# Main.net
KiCad netlist of a schematic drawn in Altium Designer
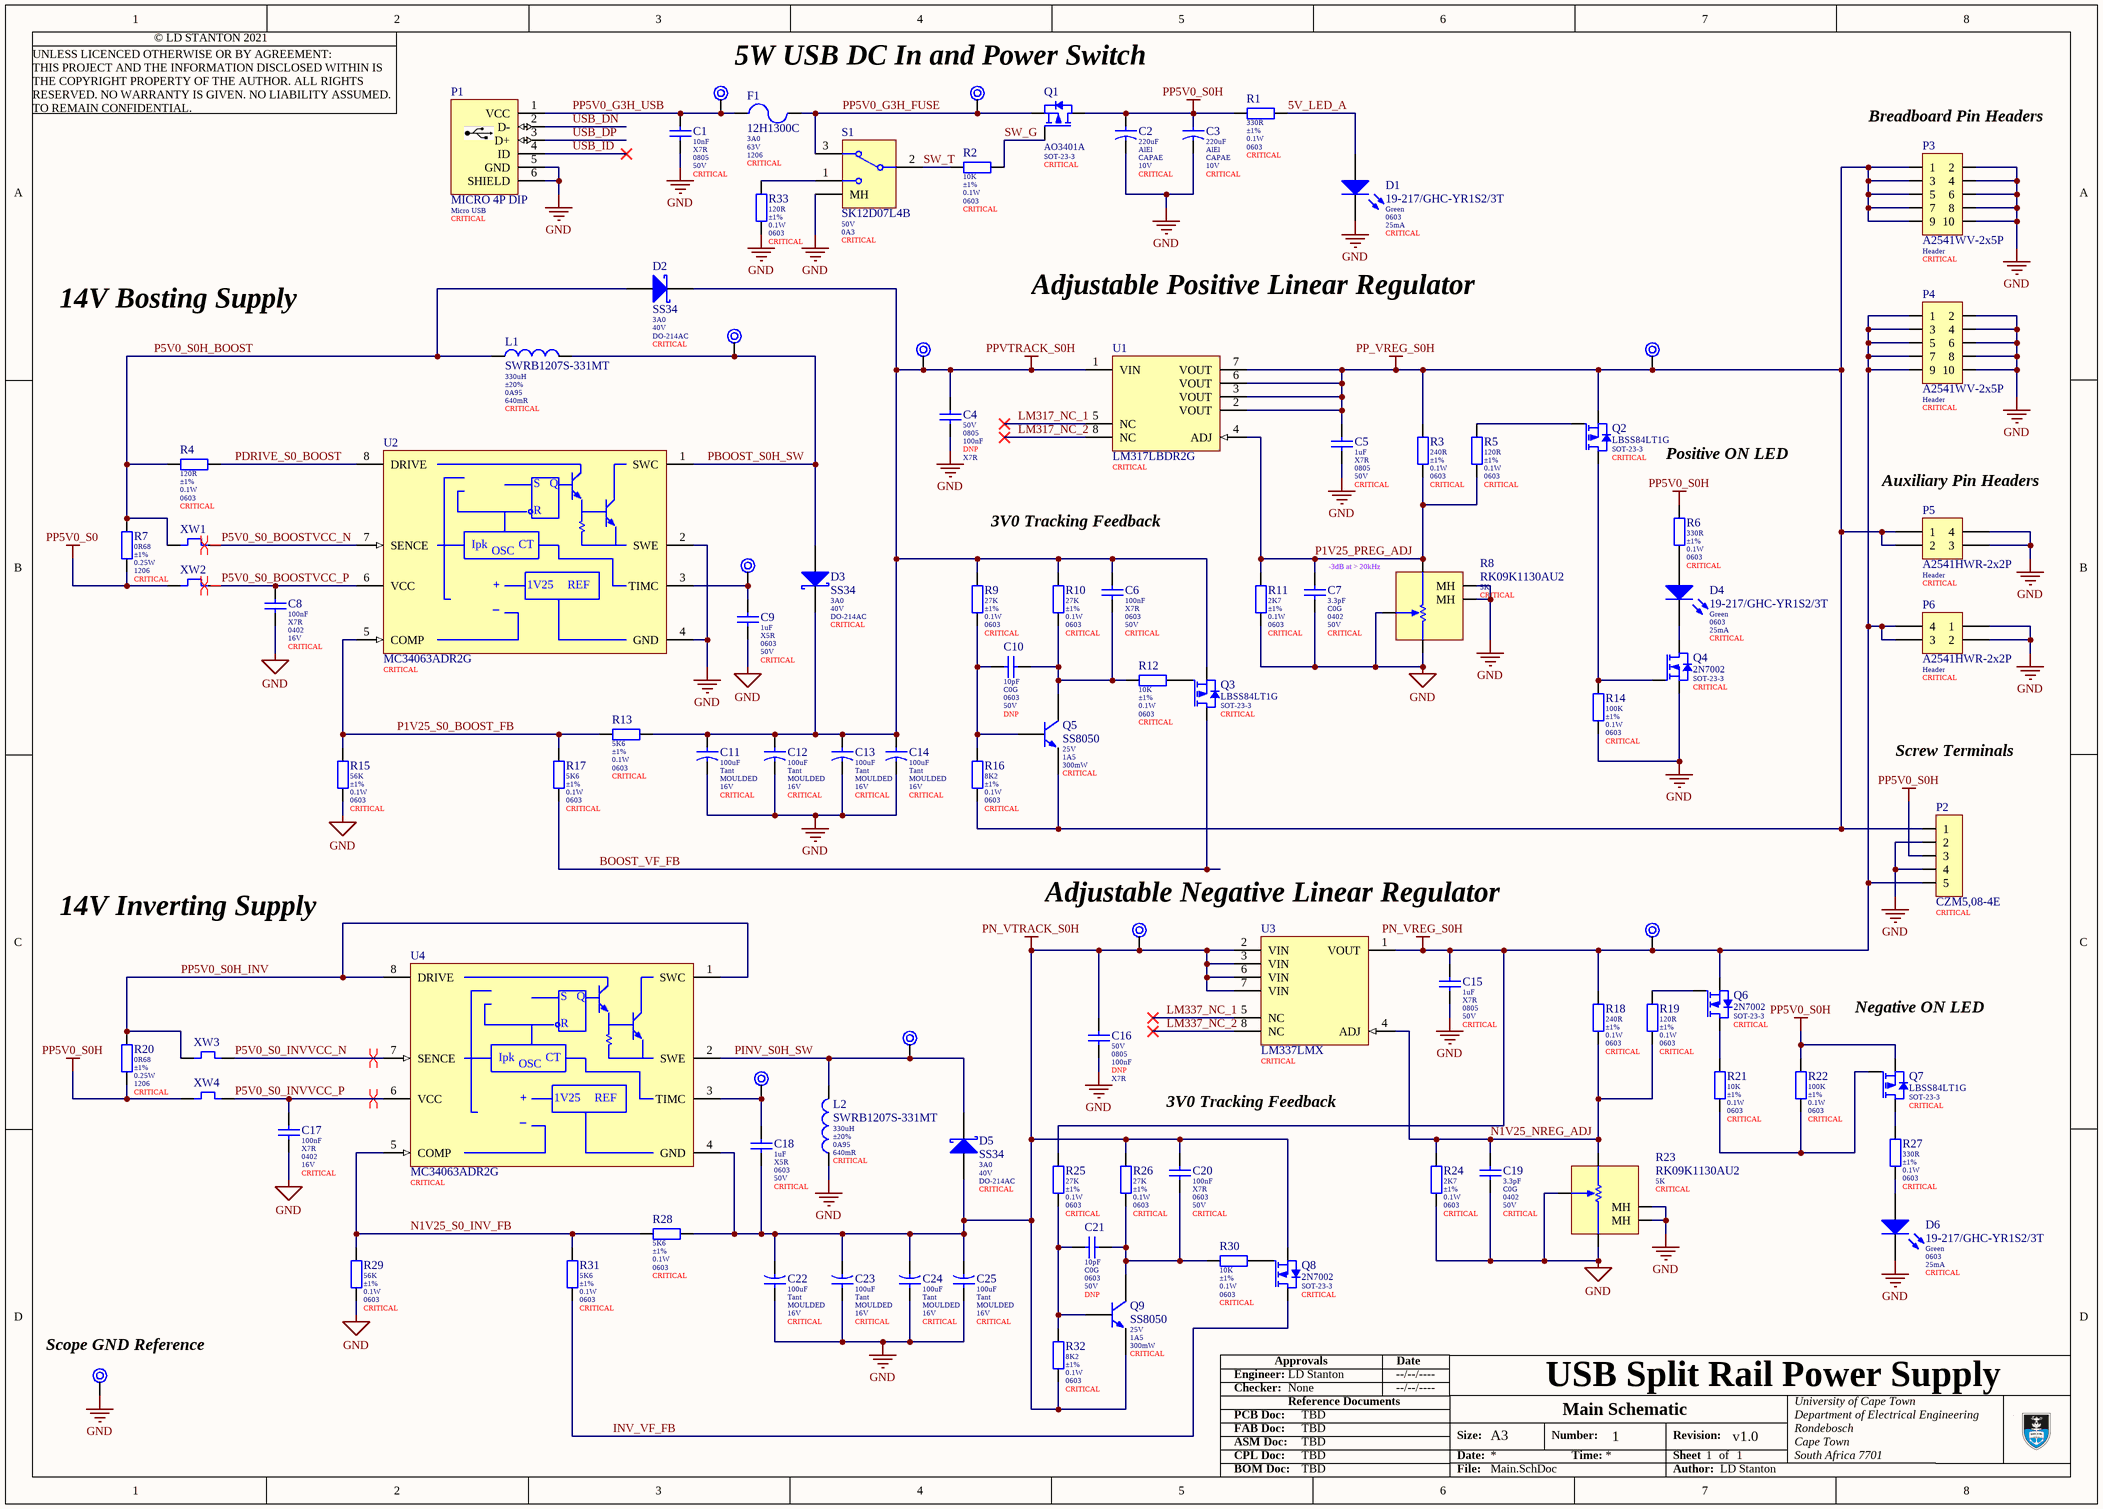
[diagram p0: Main.SchDoc]

(export (version "E")
  (design (tool "Eeschema 10.0.6"))
  (components
    (comp (ref "C1")
      (value "10nF")
      (footprint "0605_065_A_N")
      (description "MLCC 10nF 0805 50V X7R ±10%")
      (fields
        (field (name "TOLERANCE") "±10%")
        (field (name "LCSC PART NUMBER") "C1710")
        (field (name "DIELECTRIC") "X7R")
        (field (name "PACKAGE") "0805")
        (field (name "VOLTAGE") "50V")
        (field (name "POPULATE") "CRITICAL")
      )
      (libsource (lib "Samsung Capacitors") (part "MLCC 10nF 0805 50V X7R"))
    )
    (comp (ref "C2")
      (value "220uF")
      (footprint "CAPAE 6354")
      (description "Aluminium Electrolytic Capacitor 220uF CAPAE 10V ±20%")
      (fields
        (field (name "TOLERANCE") "±20%")
        (field (name "LCSC PART NUMBER") "C3345")
        (field (name "DIELECTRIC") "AlEl")
        (field (name "PACKAGE") "CAPAE")
        (field (name "VOLTAGE") "10V")
        (field (name "POPULATE") "CRITICAL")
      )
      (libsource (lib "JLCPCB Electrolytic Capacitors") (part "Cap AlEl 220uF 10V"))
    )
    (comp (ref "C3")
      (value "220uF")
      (footprint "CAPAE 6354")
      (description "Aluminium Electrolytic Capacitor 220uF CAPAE 10V ±20%")
      (fields
        (field (name "TOLERANCE") "±20%")
        (field (name "LCSC PART NUMBER") "C3345")
        (field (name "DIELECTRIC") "AlEl")
        (field (name "PACKAGE") "CAPAE")
        (field (name "VOLTAGE") "10V")
        (field (name "POPULATE") "CRITICAL")
      )
      (libsource (lib "JLCPCB Electrolytic Capacitors") (part "Cap AlEl 220uF 10V"))
    )
    (comp (ref "C4")
      (value "100nF")
      (footprint "0805")
      (description "MLCC 100nF 50V 0805 X7R ±10%")
      (fields
        (field (name "TOLERANCE") "±10%")
        (field (name "LCSC PART NUMBER") "C49678")
        (field (name "VOLTAGE") "50V")
        (field (name "PACKAGE") "0805")
        (field (name "POPULATE") "DNP")
        (field (name "DIELECTRIC") "X7R")
      )
      (libsource (lib "Yageo Capacitors") (part "MLCC 100nF 50V 0805 X7R"))
    )
    (comp (ref "C5")
      (value "1uF")
      (footprint "0805_125_F_N")
      (description "MLCC 1uF 0805 50V X7R ±10%")
      (fields
        (field (name "TOLERANCE") "±10%")
        (field (name "LCSC PART NUMBER") "C15849")
        (field (name "DIELECTRIC") "X7R")
        (field (name "PACKAGE") "0805")
        (field (name "VOLTAGE") "50V")
        (field (name "POPULATE") "CRITICAL")
      )
      (libsource (lib "Samsung Capacitors") (part "MLCC 1uF 0805 50V X7R"))
    )
    (comp (ref "C6")
      (value "100nF")
      (footprint "0603")
      (description "MLCC 100nF 50V 0603 X7R ±10%")
      (fields
        (field (name "TOLERANCE") "±10%")
        (field (name "LCSC PART NUMBER") "C14663")
        (field (name "DIELECTRIC") "X7R")
        (field (name "PACKAGE") "0603")
        (field (name "VOLTAGE") "50V")
        (field (name "POPULATE") "CRITICAL")
      )
      (libsource (lib "Yageo Capacitors") (part "MLCC 100nF 50V 0603 X7R"))
    )
    (comp (ref "C7")
      (value "3.3pF")
      (footprint "0402_050")
      (description "MLCC 3.3pF 0402 50V C0G ±0.25pF")
      (fields
        (field (name "TOLERANCE") "±0.25pF")
        (field (name "LCSC PART NUMBER") "C1565")
        (field (name "DIELECTRIC") "C0G")
        (field (name "PACKAGE") "0402")
        (field (name "VOLTAGE") "50V")
        (field (name "POPULATE") "CRITICAL")
      )
      (libsource (lib "Guangdong Capacitors") (part "MLCC 3.3pF 0402 50V C0G"))
    )
    (comp (ref "C8")
      (value "100nF")
      (footprint "0402_050_5_N")
      (description "MLCC 100nF 0402 16V X7R ±10%")
      (fields
        (field (name "TOLERANCE") "±10%")
        (field (name "LCSC PART NUMBER") "C1525")
        (field (name "DIELECTRIC") "X7R")
        (field (name "PACKAGE") "0402")
        (field (name "VOLTAGE") "16V")
        (field (name "POPULATE") "CRITICAL")
      )
      (libsource (lib "Samsung Capacitors") (part "MLCC 100nF 0402 16V X7R"))
    )
    (comp (ref "C9")
      (value "1uF")
      (footprint "0603_080_8_N")
      (description "MLCC 1uF 0603 50V X5R ±10%")
      (fields
        (field (name "TOLERANCE") "±10%")
        (field (name "LCSC PART NUMBER") "C15849")
        (field (name "DIELECTRIC") "X5R")
        (field (name "PACKAGE") "0603")
        (field (name "VOLTAGE") "50V")
        (field (name "POPULATE") "CRITICAL")
      )
      (libsource (lib "Samsung Capacitors") (part "MLCC 1uF 0603 50V X5R"))
    )
    (comp (ref "C10")
      (value "10pF")
      (footprint "0603_080_8_N")
      (description "MLCC 10pF 0603 C0G ±0.1pF")
      (fields
        (field (name "TOLERANCE") "±0.1pF")
        (field (name "LCSC PART NUMBER") "C1634")
        (field (name "DIELECTRIC") "C0G")
        (field (name "PACKAGE") "0603")
        (field (name "VOLTAGE") "50V")
        (field (name "POPULATE") "DNP")
      )
      (libsource (lib "Samsung Capacitors") (part "MLCC 10pF 0603 50V C0G"))
    )
    (comp (ref "C11")
      (value "100uF")
      (footprint "Case D")
      (description "Tantalum Capacitor 100uF 16V ±20%")
      (fields
        (field (name "TOLERANCE") "±20%")
        (field (name "LCSC PART NUMBER") "C129696")
        (field (name "DIELECTRIC") "Tant")
        (field (name "PACKAGE") "MOULDED")
        (field (name "VOLTAGE") "16V")
        (field (name "POPULATE") "CRITICAL")
      )
      (libsource (lib "Tantalums Vishay") (part "Cap Tant 100uF 16V"))
    )
    (comp (ref "C12")
      (value "100uF")
      (footprint "Case D")
      (description "Tantalum Capacitor 100uF 16V ±20%")
      (fields
        (field (name "TOLERANCE") "±20%")
        (field (name "LCSC PART NUMBER") "C129696")
        (field (name "DIELECTRIC") "Tant")
        (field (name "PACKAGE") "MOULDED")
        (field (name "VOLTAGE") "16V")
        (field (name "POPULATE") "CRITICAL")
      )
      (libsource (lib "Tantalums Vishay") (part "Cap Tant 100uF 16V"))
    )
    (comp (ref "C13")
      (value "100uF")
      (footprint "Case D")
      (description "Tantalum Capacitor 100uF 16V ±20%")
      (fields
        (field (name "TOLERANCE") "±20%")
        (field (name "LCSC PART NUMBER") "C129696")
        (field (name "DIELECTRIC") "Tant")
        (field (name "PACKAGE") "MOULDED")
        (field (name "VOLTAGE") "16V")
        (field (name "POPULATE") "CRITICAL")
      )
      (libsource (lib "Tantalums Vishay") (part "Cap Tant 100uF 16V"))
    )
    (comp (ref "C14")
      (value "100uF")
      (footprint "Case D")
      (description "Tantalum Capacitor 100uF 16V ±20%")
      (fields
        (field (name "TOLERANCE") "±20%")
        (field (name "LCSC PART NUMBER") "C129696")
        (field (name "DIELECTRIC") "Tant")
        (field (name "PACKAGE") "MOULDED")
        (field (name "VOLTAGE") "16V")
        (field (name "POPULATE") "CRITICAL")
      )
      (libsource (lib "Tantalums Vishay") (part "Cap Tant 100uF 16V"))
    )
    (comp (ref "C15")
      (value "1uF")
      (footprint "0805_125_F_N")
      (description "MLCC 1uF 0805 50V X7R ±10%")
      (fields
        (field (name "TOLERANCE") "±10%")
        (field (name "LCSC PART NUMBER") "C15849")
        (field (name "DIELECTRIC") "X7R")
        (field (name "PACKAGE") "0805")
        (field (name "VOLTAGE") "50V")
        (field (name "POPULATE") "CRITICAL")
      )
      (libsource (lib "Samsung Capacitors") (part "MLCC 1uF 0805 50V X7R"))
    )
    (comp (ref "C16")
      (value "100nF")
      (footprint "0805")
      (description "MLCC 100nF 50V 0805 X7R ±10%")
      (fields
        (field (name "TOLERANCE") "±10%")
        (field (name "LCSC PART NUMBER") "C49678")
        (field (name "VOLTAGE") "50V")
        (field (name "PACKAGE") "0805")
        (field (name "POPULATE") "DNP")
        (field (name "DIELECTRIC") "X7R")
      )
      (libsource (lib "Yageo Capacitors") (part "MLCC 100nF 50V 0805 X7R"))
    )
    (comp (ref "C17")
      (value "100nF")
      (footprint "0402_050_5_N")
      (description "MLCC 100nF 0402 16V X7R ±10%")
      (fields
        (field (name "TOLERANCE") "±10%")
        (field (name "LCSC PART NUMBER") "C1525")
        (field (name "DIELECTRIC") "X7R")
        (field (name "PACKAGE") "0402")
        (field (name "VOLTAGE") "16V")
        (field (name "POPULATE") "CRITICAL")
      )
      (libsource (lib "Samsung Capacitors") (part "MLCC 100nF 0402 16V X7R"))
    )
    (comp (ref "C18")
      (value "1uF")
      (footprint "0603_080_8_N")
      (description "MLCC 1uF 0603 50V X5R ±10%")
      (fields
        (field (name "TOLERANCE") "±10%")
        (field (name "LCSC PART NUMBER") "C15849")
        (field (name "DIELECTRIC") "X5R")
        (field (name "PACKAGE") "0603")
        (field (name "VOLTAGE") "50V")
        (field (name "POPULATE") "CRITICAL")
      )
      (libsource (lib "Samsung Capacitors") (part "MLCC 1uF 0603 50V X5R"))
    )
    (comp (ref "C19")
      (value "3.3pF")
      (footprint "0402_050")
      (description "MLCC 3.3pF 0402 50V C0G ±0.25pF")
      (fields
        (field (name "TOLERANCE") "±0.25pF")
        (field (name "LCSC PART NUMBER") "C1565")
        (field (name "DIELECTRIC") "C0G")
        (field (name "PACKAGE") "0402")
        (field (name "VOLTAGE") "50V")
        (field (name "POPULATE") "CRITICAL")
      )
      (libsource (lib "Guangdong Capacitors") (part "MLCC 3.3pF 0402 50V C0G"))
    )
    (comp (ref "C20")
      (value "100nF")
      (footprint "0603")
      (description "MLCC 100nF 50V 0603 X7R ±10%")
      (fields
        (field (name "TOLERANCE") "±10%")
        (field (name "LCSC PART NUMBER") "C14663")
        (field (name "DIELECTRIC") "X7R")
        (field (name "PACKAGE") "0603")
        (field (name "VOLTAGE") "50V")
        (field (name "POPULATE") "CRITICAL")
      )
      (libsource (lib "Yageo Capacitors") (part "MLCC 100nF 50V 0603 X7R"))
    )
    (comp (ref "C21")
      (value "10pF")
      (footprint "0603_080_8_N")
      (description "MLCC 10pF 0603 C0G ±0.1pF")
      (fields
        (field (name "TOLERANCE") "±0.1pF")
        (field (name "LCSC PART NUMBER") "C1634")
        (field (name "DIELECTRIC") "C0G")
        (field (name "PACKAGE") "0603")
        (field (name "VOLTAGE") "50V")
        (field (name "POPULATE") "DNP")
      )
      (libsource (lib "Samsung Capacitors") (part "MLCC 10pF 0603 50V C0G"))
    )
    (comp (ref "C22")
      (value "100uF")
      (footprint "Case D")
      (description "Tantalum Capacitor 100uF 16V ±20%")
      (fields
        (field (name "TOLERANCE") "±20%")
        (field (name "LCSC PART NUMBER") "C129696")
        (field (name "DIELECTRIC") "Tant")
        (field (name "PACKAGE") "MOULDED")
        (field (name "VOLTAGE") "16V")
        (field (name "POPULATE") "CRITICAL")
      )
      (libsource (lib "Tantalums Vishay") (part "Cap Tant 100uF 16V"))
    )
    (comp (ref "C23")
      (value "100uF")
      (footprint "Case D")
      (description "Tantalum Capacitor 100uF 16V ±20%")
      (fields
        (field (name "TOLERANCE") "±20%")
        (field (name "LCSC PART NUMBER") "C129696")
        (field (name "DIELECTRIC") "Tant")
        (field (name "PACKAGE") "MOULDED")
        (field (name "VOLTAGE") "16V")
        (field (name "POPULATE") "CRITICAL")
      )
      (libsource (lib "Tantalums Vishay") (part "Cap Tant 100uF 16V"))
    )
    (comp (ref "C24")
      (value "100uF")
      (footprint "Case D")
      (description "Tantalum Capacitor 100uF 16V ±20%")
      (fields
        (field (name "TOLERANCE") "±20%")
        (field (name "LCSC PART NUMBER") "C129696")
        (field (name "DIELECTRIC") "Tant")
        (field (name "PACKAGE") "MOULDED")
        (field (name "VOLTAGE") "16V")
        (field (name "POPULATE") "CRITICAL")
      )
      (libsource (lib "Tantalums Vishay") (part "Cap Tant 100uF 16V"))
    )
    (comp (ref "C25")
      (value "100uF")
      (footprint "Case D")
      (description "Tantalum Capacitor 100uF 16V ±20%")
      (fields
        (field (name "TOLERANCE") "±20%")
        (field (name "LCSC PART NUMBER") "C129696")
        (field (name "DIELECTRIC") "Tant")
        (field (name "PACKAGE") "MOULDED")
        (field (name "VOLTAGE") "16V")
        (field (name "POPULATE") "CRITICAL")
      )
      (libsource (lib "Tantalums Vishay") (part "Cap Tant 100uF 16V"))
    )
    (comp (ref "D1")
      (value "19-217/GHC-YR1S2/3T")
      (footprint "LED 0603")
      (description "LED 0603 SMT Green")
      (fields
        (field (name "LCSC PART NUMBER") "C72043")
        (field (name "COLOUR") "Green")
        (field (name "PACKAGE") "0603")
        (field (name "CURRENT") "25mA")
        (field (name "PLACEMENT") "CRITICAL")
      )
      (libsource (lib "JLCPCB LEDs") (part "LED 0603 Green"))
    )
    (comp (ref "D2")
      (value "SS34")
      (footprint "DO-214AC")
      (description "Schottky Barrier Diode 40V 3A0 550mV")
      (fields
        (field (name "LCSC PART NUMBER") "C8678")
        (field (name "MANUFACTURER") "MDD")
        (field (name "DC FORWARD CURENT") "3A0")
        (field (name "DC REVERSE BLOCKING") "40V")
        (field (name "PACKAGE") "DO-214AC")
        (field (name "PLACEMENT") "CRITICAL")
      )
      (libsource (lib "Schottky Barrier Diodes") (part "SS34"))
    )
    (comp (ref "D3")
      (value "SS34")
      (footprint "DO-214AC")
      (description "Schottky Barrier Diode 40V 3A0 550mV")
      (fields
        (field (name "LCSC PART NUMBER") "C8678")
        (field (name "MANUFACTURER") "MDD")
        (field (name "DC FORWARD CURENT") "3A0")
        (field (name "DC REVERSE BLOCKING") "40V")
        (field (name "PACKAGE") "DO-214AC")
        (field (name "PLACEMENT") "CRITICAL")
      )
      (libsource (lib "Schottky Barrier Diodes") (part "SS34"))
    )
    (comp (ref "D4")
      (value "19-217/GHC-YR1S2/3T")
      (footprint "LED 0603")
      (description "LED 0603 SMT Green")
      (fields
        (field (name "LCSC PART NUMBER") "C72043")
        (field (name "COLOUR") "Green")
        (field (name "PACKAGE") "0603")
        (field (name "CURRENT") "25mA")
        (field (name "PLACEMENT") "CRITICAL")
      )
      (libsource (lib "JLCPCB LEDs") (part "LED 0603 Green"))
    )
    (comp (ref "D5")
      (value "SS34")
      (footprint "DO-214AC")
      (description "Schottky Barrier Diode 40V 3A0 550mV")
      (fields
        (field (name "LCSC PART NUMBER") "C8678")
        (field (name "MANUFACTURER") "MDD")
        (field (name "DC FORWARD CURENT") "3A0")
        (field (name "DC REVERSE BLOCKING") "40V")
        (field (name "PACKAGE") "DO-214AC")
        (field (name "PLACEMENT") "CRITICAL")
      )
      (libsource (lib "Schottky Barrier Diodes") (part "SS34"))
    )
    (comp (ref "D6")
      (value "19-217/GHC-YR1S2/3T")
      (footprint "LED 0603")
      (description "LED 0603 SMT Green")
      (fields
        (field (name "LCSC PART NUMBER") "C72043")
        (field (name "COLOUR") "Green")
        (field (name "PACKAGE") "0603")
        (field (name "CURRENT") "25mA")
        (field (name "PLACEMENT") "CRITICAL")
      )
      (libsource (lib "JLCPCB LEDs") (part "LED 0603 Green"))
    )
    (comp (ref "F1")
      (value "12H1300C")
      (footprint "1206_060")
      (description "Fuse SMD Slow Blow 3A 63VAC 1206")
      (fields
        (field (name "LCSC PART NUMBER") "C182445")
        (field (name "CURRENT") "3A0")
        (field (name "VOLTAGE") "63V")
        (field (name "PACKAGE") "1206")
        (field (name "PLACEMENT") "CRITICAL")
      )
      (libsource (lib "Fuses") (part "Fuse 3A Slow 1206"))
    )
    (comp (ref "L1")
      (value "SWRB1207S-331MT")
      (footprint "SWRB1207S")
      (description "Inductor 330uH ±20% 0A95 640mR Moulded SMD 12.5x12.5x8.0mm")
      (fields
        (field (name "LCSC PART NUMBER") "C169381")
        (field (name "MANUFACTURER") "Sunlord")
        (field (name "ALTIUM_VALUE") "330uH")
        (field (name "TOLERANCE") "±20%")
        (field (name "RATED CURRENT") "0A95")
        (field (name "DC RESISTANCE") "640mR")
        (field (name "POPULATE") "CRITICAL")
      )
      (libsource (lib "JLCPCB Inductors") (part "Inductor 330uH ±20% 0A95"))
    )
    (comp (ref "L2")
      (value "SWRB1207S-331MT")
      (footprint "SWRB1207S")
      (description "Inductor 330uH ±20% 0A95 640mR Moulded SMD 12.5x12.5x8.0mm")
      (fields
        (field (name "LCSC PART NUMBER") "C169381")
        (field (name "MANUFACTURER") "Sunlord")
        (field (name "ALTIUM_VALUE") "330uH")
        (field (name "TOLERANCE") "±20%")
        (field (name "RATED CURRENT") "0A95")
        (field (name "DC RESISTANCE") "640mR")
        (field (name "POPULATE") "CRITICAL")
      )
      (libsource (lib "JLCPCB Inductors") (part "Inductor 330uH ±20% 0A95"))
    )
    (comp (ref "P1")
      (value "MICRO 4P DIP")
      (footprint "MICRO 4P DIP")
      (description "Micro USB Connector SMT with TH Mounts")
      (fields
        (field (name "LCSC PART NUMBER") "C456008")
        (field (name "USB CONNECTOR TYPE") "Micro USB")
        (field (name "PLACEMENT") "CRITICAL")
      )
      (libsource (lib "USB Connectors") (part "MICRO 4P DIP"))
    )
    (comp (ref "P2")
      (value "CZM5,08-4E")
      (footprint "Screw Down 5")
      (description "Screw Down Terminal 5 Way 5.08mm Pitch")
      (fields (field (name "PLACEMENT") "CRITICAL"))
      (libsource (lib "Connectors") (part "Screw Down 5 Way 5.08mm"))
    )
    (comp (ref "P3")
      (value "A2541WV-2x5P")
      (footprint "Pin Header 10 2 Vertical Male")
      (description "Pin Header 10 Way Double Row Vertical Angle")
      (fields
        (field (name "TYPE") "Header")
        (field (name "PLACEMENT") "CRITICAL")
        (field (name "LCSC PART NUMBER") "C225520")
      )
      (libsource (lib "JLCPCB Pin Headers") (part "Pin Header 10 2 Male Vertical"))
    )
    (comp (ref "P4")
      (value "A2541WV-2x5P")
      (footprint "Pin Header 10 2 Vertical Male")
      (description "Pin Header 10 Way Double Row Vertical Angle")
      (fields
        (field (name "TYPE") "Header")
        (field (name "PLACEMENT") "CRITICAL")
        (field (name "LCSC PART NUMBER") "C225520")
      )
      (libsource (lib "JLCPCB Pin Headers") (part "Pin Header 10 2 Male Vertical"))
    )
    (comp (ref "P5")
      (value "A2541HWR-2x2P")
      (footprint "Pin Header 4 2 Right Female")
      (description "Pin Header 4 Way Double Row Female Right Angle")
      (fields (field (name "TYPE") "Header") (field (name "PLACEMENT") "CRITICAL"))
      (libsource (lib "JLCPCB Pin Headers") (part "Pin Header 4 2 Female Right"))
    )
    (comp (ref "P6")
      (value "A2541HWR-2x2P")
      (footprint "Pin Header 4 2 Right Female")
      (description "Pin Header 4 Way Double Row Female Right Angle")
      (fields (field (name "TYPE") "Header") (field (name "PLACEMENT") "CRITICAL"))
      (libsource (lib "") (part "Pin Header 4 2 Female Right_1"))
    )
    (comp (ref "Q1")
      (value "AO3401A")
      (footprint "SOT-23-3 (2N7002)")
      (description "MOSFET Trench 4A0 30V 85mR ±12V P-Channel Enhancement AOS SOT-22-3L")
      (fields
        (field (name "POWER") "0.9W")
        (field (name "LCSC PART NUMBER") "C15127")
        (field (name "PACKAGE") "SOT-23-3")
        (field (name "PLACEMENT") "CRITICAL")
      )
      (libsource (lib "MOSFETs") (part "AO3401A"))
    )
    (comp (ref "Q2")
      (value "LBSS84LT1G")
      (footprint "SOT-23-3 (2N7002)")
      (description "Small Signal MOSFET, 130 mA, 50 V, P-Channel, Enhancement, LRC SOT-23-3")
      (fields
        (field (name "POWER") "0.225W")
        (field (name "LCSC PART NUMBER") "C8492")
        (field (name "PACKAGE") "SOT-23-3")
        (field (name "PLACEMENT") "CRITICAL")
      )
      (libsource (lib "JLCPCB Transistors") (part "LBSS84LT1G"))
    )
    (comp (ref "Q3")
      (value "LBSS84LT1G")
      (footprint "SOT-23-3 (2N7002)")
      (description "Small Signal MOSFET, 130 mA, 50 V, P-Channel, Enhancement, LRC SOT-23-3")
      (fields
        (field (name "POWER") "0.225W")
        (field (name "LCSC PART NUMBER") "C8492")
        (field (name "PACKAGE") "SOT-23-3")
        (field (name "PLACEMENT") "CRITICAL")
      )
      (libsource (lib "JLCPCB Transistors") (part "LBSS84LT1G"))
    )
    (comp (ref "Q4")
      (value "2N7002")
      (footprint "SOT-23-3 (2N7002)")
      (description "Small Signal MOSFET, 500 mA, 60 V, N-Channel, Enhancement, JCET SOT-23-3")
      (fields
        (field (name "POWER") "0.225W")
        (field (name "LCSC PART NUMBER") "C8545")
        (field (name "PACKAGE") "SOT-23-3")
        (field (name "PLACEMENT") "CRITICAL")
      )
      (libsource (lib "JLCPCB Transistors") (part "2N7002"))
    )
    (comp (ref "Q5")
      (value "SS8050")
      (footprint "SOT-23-3 Generic")
      (description "BJT NPN 1A5 25V SOT-23-3")
      (fields
        (field (name "MANUFACTURER") "Changjiang Electronics")
        (field (name "LCSC PART NUMBER") "C2150")
        (field (name "VCE") "25V")
        (field (name "COLLECTOR CURRENT") "1A5")
        (field (name "POWER") "300mW")
        (field (name "PLACEMENT") "CRITICAL")
      )
      (libsource (lib "JLCPCB Transistors") (part "SS8050"))
    )
    (comp (ref "Q6")
      (value "2N7002")
      (footprint "SOT-23-3 (2N7002)")
      (description "Small Signal MOSFET, 500 mA, 60 V, N-Channel, Enhancement, JCET SOT-23-3")
      (fields
        (field (name "POWER") "0.225W")
        (field (name "LCSC PART NUMBER") "C8545")
        (field (name "PACKAGE") "SOT-23-3")
        (field (name "PLACEMENT") "CRITICAL")
      )
      (libsource (lib "JLCPCB Transistors") (part "2N7002"))
    )
    (comp (ref "Q7")
      (value "LBSS84LT1G")
      (footprint "SOT-23-3 (2N7002)")
      (description "Small Signal MOSFET, 130 mA, 50 V, P-Channel, Enhancement, LRC SOT-23-3")
      (fields
        (field (name "POWER") "0.225W")
        (field (name "LCSC PART NUMBER") "C8492")
        (field (name "PACKAGE") "SOT-23-3")
        (field (name "PLACEMENT") "CRITICAL")
      )
      (libsource (lib "JLCPCB Transistors") (part "LBSS84LT1G"))
    )
    (comp (ref "Q8")
      (value "2N7002")
      (footprint "SOT-23-3 (2N7002)")
      (description "Small Signal MOSFET, 500 mA, 60 V, N-Channel, Enhancement, JCET SOT-23-3")
      (fields
        (field (name "POWER") "0.225W")
        (field (name "LCSC PART NUMBER") "C8545")
        (field (name "PACKAGE") "SOT-23-3")
        (field (name "PLACEMENT") "CRITICAL")
      )
      (libsource (lib "JLCPCB Transistors") (part "2N7002"))
    )
    (comp (ref "Q9")
      (value "SS8050")
      (footprint "SOT-23-3 Generic")
      (description "BJT NPN 1A5 25V SOT-23-3")
      (fields
        (field (name "MANUFACTURER") "Changjiang Electronics")
        (field (name "LCSC PART NUMBER") "C2150")
        (field (name "VCE") "25V")
        (field (name "COLLECTOR CURRENT") "1A5")
        (field (name "POWER") "300mW")
        (field (name "PLACEMENT") "CRITICAL")
      )
      (libsource (lib "JLCPCB Transistors") (part "SS8050"))
    )
    (comp (ref "R1")
      (value "330R")
      (footprint "0603")
      (description "Lead Free Thick Film Chip Resistor 0805 ±1%")
      (fields
        (field (name "LCSC PART NUMBER") "C23138")
        (field (name "TOLERANCE") "±1%")
        (field (name "POWER") "0.1W")
        (field (name "PACKAGE") "0603")
        (field (name "POPULATE") "CRITICAL")
        (field (name "Comment") "0603WAF3300T5E")
      )
      (libsource (lib "Uniroyal Resistors") (part "Res 330R 0603"))
    )
    (comp (ref "R2")
      (value "10K")
      (footprint "0603")
      (description "Lead Free Thick Film Chip Resistor 0603 ±1%")
      (fields
        (field (name "LCSC PART NUMBER") "C25804")
        (field (name "TOLERANCE") "±1%")
        (field (name "POWER") "0.1W")
        (field (name "PACKAGE") "0603")
        (field (name "POPULATE") "CRITICAL")
        (field (name "Comment") "0603WAF1002T5E")
      )
      (libsource (lib "Uniroyal Resistors") (part "Res 10K 0603"))
    )
    (comp (ref "R3")
      (value "240R")
      (footprint "0603")
      (description "Lead Free Thick Film Chip Resistor 0603 ±1%")
      (fields
        (field (name "LCSC PART NUMBER") "C23350")
        (field (name "TOLERANCE") "±1%")
        (field (name "POWER") "0.1W")
        (field (name "PACKAGE") "0603")
        (field (name "POPULATE") "CRITICAL")
        (field (name "Comment") "0603WAF2400T5E")
      )
      (libsource (lib "Uniroyal Resistors") (part "Res 240R 0603"))
    )
    (comp (ref "R4")
      (value "120R")
      (footprint "0603")
      (description "Lead Free Thick Film Chip Resistor 0603 ±1%")
      (fields
        (field (name "LCSC PART NUMBER") "C22787")
        (field (name "TOLERANCE") "±1%")
        (field (name "POWER") "0.1W")
        (field (name "PACKAGE") "0603")
        (field (name "POPULATE") "CRITICAL")
        (field (name "Comment") "0603WAF1200T5E")
      )
      (libsource (lib "Uniroyal Resistors") (part "Res 120R 0603"))
    )
    (comp (ref "R5")
      (value "120R")
      (footprint "0603")
      (description "Lead Free Thick Film Chip Resistor 0603 ±1%")
      (fields
        (field (name "LCSC PART NUMBER") "C22787")
        (field (name "TOLERANCE") "±1%")
        (field (name "POWER") "0.1W")
        (field (name "PACKAGE") "0603")
        (field (name "POPULATE") "CRITICAL")
        (field (name "Comment") "0603WAF1200T5E")
      )
      (libsource (lib "Uniroyal Resistors") (part "Res 120R 0603"))
    )
    (comp (ref "R6")
      (value "330R")
      (footprint "0603")
      (description "Lead Free Thick Film Chip Resistor 0805 ±1%")
      (fields
        (field (name "LCSC PART NUMBER") "C23138")
        (field (name "TOLERANCE") "±1%")
        (field (name "POWER") "0.1W")
        (field (name "PACKAGE") "0603")
        (field (name "POPULATE") "CRITICAL")
        (field (name "Comment") "0603WAF3300T5E")
      )
      (libsource (lib "Uniroyal Resistors") (part "Res 330R 0603"))
    )
    (comp (ref "R7")
      (value "0R68")
      (footprint "1206")
      (description "Lead Free Thick Film Chip Resistor 1206 ±1%")
      (fields
        (field (name "LCSC PART NUMBER") "C19108")
        (field (name "TOLERANCE") "±1%")
        (field (name "POWER") "0.25W")
        (field (name "PACKAGE") "1206")
        (field (name "POPULATE") "CRITICAL")
        (field (name "Comment") "1206W4F680LT5E")
      )
      (libsource (lib "Uniroyal Resistors") (part "Res 0R68 1206"))
    )
    (comp (ref "R8")
      (value "RK09K1130AU2")
      (footprint "RK09K113")
      (description "5K Potentiometer THT 9.8mm Diameter ±20% 20VDC")
      (fields
        (field (name "MANUFACTURER") "Alpsalpine")
        (field (name "RESISTANCE") "5K")
        (field (name "PLACEMENT") "CRITICAL")
        (field (name "LCSC PART NUMBER") "C388855")
      )
      (libsource (lib "") (part "Pot 5K THT 9.8mm_1"))
    )
    (comp (ref "R9")
      (value "27K")
      (footprint "0603")
      (description "Lead Free Thick Film Chip Resistor 0603 ±1%")
      (fields
        (field (name "LCSC PART NUMBER") "C22967")
        (field (name "TOLERANCE") "±1%")
        (field (name "POWER") "0.1W")
        (field (name "PACKAGE") "0603")
        (field (name "POPULATE") "CRITICAL")
        (field (name "Comment") "0603WAF2702T5E")
      )
      (libsource (lib "Uniroyal Resistors") (part "Res 27K 0603"))
    )
    (comp (ref "R10")
      (value "27K")
      (footprint "0603")
      (description "Lead Free Thick Film Chip Resistor 0603 ±1%")
      (fields
        (field (name "LCSC PART NUMBER") "C22967")
        (field (name "TOLERANCE") "±1%")
        (field (name "POWER") "0.1W")
        (field (name "PACKAGE") "0603")
        (field (name "POPULATE") "CRITICAL")
        (field (name "Comment") "0603WAF2702T5E")
      )
      (libsource (lib "Uniroyal Resistors") (part "Res 27K 0603"))
    )
    (comp (ref "R11")
      (value "2K7")
      (footprint "0603")
      (description "Lead Free Thick Film Chip Resistor 0603 ±1%")
      (fields
        (field (name "LCSC PART NUMBER") "C13167")
        (field (name "TOLERANCE") "±1%")
        (field (name "POWER") "0.1W")
        (field (name "PACKAGE") "0603")
        (field (name "POPULATE") "CRITICAL")
        (field (name "Comment") "0603WAF2701T5E")
      )
      (libsource (lib "Uniroyal Resistors") (part "Res 2K7 0603"))
    )
    (comp (ref "R12")
      (value "10K")
      (footprint "0603")
      (description "Lead Free Thick Film Chip Resistor 0603 ±1%")
      (fields
        (field (name "LCSC PART NUMBER") "C25804")
        (field (name "TOLERANCE") "±1%")
        (field (name "POWER") "0.1W")
        (field (name "PACKAGE") "0603")
        (field (name "POPULATE") "CRITICAL")
        (field (name "Comment") "0603WAF1002T5E")
      )
      (libsource (lib "Uniroyal Resistors") (part "Res 10K 0603"))
    )
    (comp (ref "R13")
      (value "5K6")
      (footprint "0603")
      (description "Lead Free Thick Film Chip Resistor 0603 ±1%")
      (fields
        (field (name "LCSC PART NUMBER") "C23189")
        (field (name "TOLERANCE") "±1%")
        (field (name "POWER") "0.1W")
        (field (name "PACKAGE") "0603")
        (field (name "POPULATE") "CRITICAL")
        (field (name "Comment") "0603WAF5601T5E")
      )
      (libsource (lib "Uniroyal Resistors") (part "Res 5K6 0603"))
    )
    (comp (ref "R14")
      (value "100K")
      (footprint "0603")
      (description "Lead Free Thick Film Chip Resistor 0603 ±1%")
      (fields
        (field (name "LCSC PART NUMBER") "C25803")
        (field (name "TOLERANCE") "±1%")
        (field (name "POWER") "0.1W")
        (field (name "PACKAGE") "0603")
        (field (name "POPULATE") "CRITICAL")
        (field (name "Comment") "0603WAF1003T5E")
      )
      (libsource (lib "Uniroyal Resistors") (part "Res 100K 0603"))
    )
    (comp (ref "R15")
      (value "56K")
      (footprint "0603")
      (description "Lead Free Thick Film Chip Resistor 0603 ±1%")
      (fields
        (field (name "LCSC PART NUMBER") "C23206")
        (field (name "TOLERANCE") "±1%")
        (field (name "POWER") "0.1W")
        (field (name "PACKAGE") "0603")
        (field (name "POPULATE") "CRITICAL")
        (field (name "Comment") "0603WAF5602T5E")
      )
      (libsource (lib "Uniroyal Resistors") (part "Res 56K 0603"))
    )
    (comp (ref "R16")
      (value "8K2")
      (footprint "0603")
      (description "Lead Free Thick Film Chip Resistor 0603 ±1%")
      (fields
        (field (name "LCSC PART NUMBER") "C25981")
        (field (name "TOLERANCE") "±1%")
        (field (name "POWER") "0.1W")
        (field (name "PACKAGE") "0603")
        (field (name "POPULATE") "CRITICAL")
        (field (name "Comment") "0603WAF8201T5E")
      )
      (libsource (lib "Uniroyal Resistors") (part "Res 8K2 0603"))
    )
    (comp (ref "R17")
      (value "5K6")
      (footprint "0603")
      (description "Lead Free Thick Film Chip Resistor 0603 ±1%")
      (fields
        (field (name "LCSC PART NUMBER") "C23189")
        (field (name "TOLERANCE") "±1%")
        (field (name "POWER") "0.1W")
        (field (name "PACKAGE") "0603")
        (field (name "POPULATE") "CRITICAL")
        (field (name "Comment") "0603WAF5601T5E")
      )
      (libsource (lib "Uniroyal Resistors") (part "Res 5K6 0603"))
    )
    (comp (ref "R18")
      (value "240R")
      (footprint "0603")
      (description "Lead Free Thick Film Chip Resistor 0603 ±1%")
      (fields
        (field (name "LCSC PART NUMBER") "C23350")
        (field (name "TOLERANCE") "±1%")
        (field (name "POWER") "0.1W")
        (field (name "PACKAGE") "0603")
        (field (name "POPULATE") "CRITICAL")
        (field (name "Comment") "0603WAF2400T5E")
      )
      (libsource (lib "Uniroyal Resistors") (part "Res 240R 0603"))
    )
    (comp (ref "R19")
      (value "120R")
      (footprint "0603")
      (description "Lead Free Thick Film Chip Resistor 0603 ±1%")
      (fields
        (field (name "LCSC PART NUMBER") "C22787")
        (field (name "TOLERANCE") "±1%")
        (field (name "POWER") "0.1W")
        (field (name "PACKAGE") "0603")
        (field (name "POPULATE") "CRITICAL")
        (field (name "Comment") "0603WAF1200T5E")
      )
      (libsource (lib "Uniroyal Resistors") (part "Res 120R 0603"))
    )
    (comp (ref "R20")
      (value "0R68")
      (footprint "1206")
      (description "Lead Free Thick Film Chip Resistor 1206 ±1%")
      (fields
        (field (name "LCSC PART NUMBER") "C19108")
        (field (name "TOLERANCE") "±1%")
        (field (name "POWER") "0.25W")
        (field (name "PACKAGE") "1206")
        (field (name "POPULATE") "CRITICAL")
        (field (name "Comment") "1206W4F680LT5E")
      )
      (libsource (lib "Uniroyal Resistors") (part "Res 0R68 1206"))
    )
    (comp (ref "R21")
      (value "10K")
      (footprint "0603")
      (description "Lead Free Thick Film Chip Resistor 0603 ±1%")
      (fields
        (field (name "LCSC PART NUMBER") "C25804")
        (field (name "TOLERANCE") "±1%")
        (field (name "POWER") "0.1W")
        (field (name "PACKAGE") "0603")
        (field (name "POPULATE") "CRITICAL")
        (field (name "Comment") "0603WAF1002T5E")
      )
      (libsource (lib "Uniroyal Resistors") (part "Res 10K 0603"))
    )
    (comp (ref "R22")
      (value "100K")
      (footprint "0603")
      (description "Lead Free Thick Film Chip Resistor 0603 ±1%")
      (fields
        (field (name "LCSC PART NUMBER") "C25803")
        (field (name "TOLERANCE") "±1%")
        (field (name "POWER") "0.1W")
        (field (name "PACKAGE") "0603")
        (field (name "POPULATE") "CRITICAL")
        (field (name "Comment") "0603WAF1003T5E")
      )
      (libsource (lib "Uniroyal Resistors") (part "Res 100K 0603"))
    )
    (comp (ref "R23")
      (value "RK09K1130AU2")
      (footprint "RK09K113")
      (description "5K Potentiometer THT 9.8mm Diameter ±20% 20VDC")
      (fields
        (field (name "MANUFACTURER") "Alpsalpine")
        (field (name "RESISTANCE") "5K")
        (field (name "PLACEMENT") "CRITICAL")
        (field (name "LCSC PART NUMBER") "C388855")
      )
      (libsource (lib "Potentiometers") (part "Pot 5K THT 9.8mm"))
    )
    (comp (ref "R24")
      (value "2K7")
      (footprint "0603")
      (description "Lead Free Thick Film Chip Resistor 0603 ±1%")
      (fields
        (field (name "LCSC PART NUMBER") "C13167")
        (field (name "TOLERANCE") "±1%")
        (field (name "POWER") "0.1W")
        (field (name "PACKAGE") "0603")
        (field (name "POPULATE") "CRITICAL")
        (field (name "Comment") "0603WAF2701T5E")
      )
      (libsource (lib "Uniroyal Resistors") (part "Res 2K7 0603"))
    )
    (comp (ref "R25")
      (value "27K")
      (footprint "0603")
      (description "Lead Free Thick Film Chip Resistor 0603 ±1%")
      (fields
        (field (name "LCSC PART NUMBER") "C22967")
        (field (name "TOLERANCE") "±1%")
        (field (name "POWER") "0.1W")
        (field (name "PACKAGE") "0603")
        (field (name "POPULATE") "CRITICAL")
        (field (name "Comment") "0603WAF2702T5E")
      )
      (libsource (lib "Uniroyal Resistors") (part "Res 27K 0603"))
    )
    (comp (ref "R26")
      (value "27K")
      (footprint "0603")
      (description "Lead Free Thick Film Chip Resistor 0603 ±1%")
      (fields
        (field (name "LCSC PART NUMBER") "C22967")
        (field (name "TOLERANCE") "±1%")
        (field (name "POWER") "0.1W")
        (field (name "PACKAGE") "0603")
        (field (name "POPULATE") "CRITICAL")
        (field (name "Comment") "0603WAF2702T5E")
      )
      (libsource (lib "Uniroyal Resistors") (part "Res 27K 0603"))
    )
    (comp (ref "R27")
      (value "330R")
      (footprint "0603")
      (description "Lead Free Thick Film Chip Resistor 0805 ±1%")
      (fields
        (field (name "LCSC PART NUMBER") "C23138")
        (field (name "TOLERANCE") "±1%")
        (field (name "POWER") "0.1W")
        (field (name "PACKAGE") "0603")
        (field (name "POPULATE") "CRITICAL")
        (field (name "Comment") "0603WAF3300T5E")
      )
      (libsource (lib "Uniroyal Resistors") (part "Res 330R 0603"))
    )
    (comp (ref "R28")
      (value "5K6")
      (footprint "0603")
      (description "Lead Free Thick Film Chip Resistor 0603 ±1%")
      (fields
        (field (name "LCSC PART NUMBER") "C23189")
        (field (name "TOLERANCE") "±1%")
        (field (name "POWER") "0.1W")
        (field (name "PACKAGE") "0603")
        (field (name "POPULATE") "CRITICAL")
        (field (name "Comment") "0603WAF5601T5E")
      )
      (libsource (lib "Uniroyal Resistors") (part "Res 5K6 0603"))
    )
    (comp (ref "R29")
      (value "56K")
      (footprint "0603")
      (description "Lead Free Thick Film Chip Resistor 0603 ±1%")
      (fields
        (field (name "LCSC PART NUMBER") "C23206")
        (field (name "TOLERANCE") "±1%")
        (field (name "POWER") "0.1W")
        (field (name "PACKAGE") "0603")
        (field (name "POPULATE") "CRITICAL")
        (field (name "Comment") "0603WAF5602T5E")
      )
      (libsource (lib "Uniroyal Resistors") (part "Res 56K 0603"))
    )
    (comp (ref "R30")
      (value "10K")
      (footprint "0603")
      (description "Lead Free Thick Film Chip Resistor 0603 ±1%")
      (fields
        (field (name "LCSC PART NUMBER") "C25804")
        (field (name "TOLERANCE") "±1%")
        (field (name "POWER") "0.1W")
        (field (name "PACKAGE") "0603")
        (field (name "POPULATE") "CRITICAL")
        (field (name "Comment") "0603WAF1002T5E")
      )
      (libsource (lib "Uniroyal Resistors") (part "Res 10K 0603"))
    )
    (comp (ref "R31")
      (value "5K6")
      (footprint "0603")
      (description "Lead Free Thick Film Chip Resistor 0603 ±1%")
      (fields
        (field (name "LCSC PART NUMBER") "C23189")
        (field (name "TOLERANCE") "±1%")
        (field (name "POWER") "0.1W")
        (field (name "PACKAGE") "0603")
        (field (name "POPULATE") "CRITICAL")
        (field (name "Comment") "0603WAF5601T5E")
      )
      (libsource (lib "Uniroyal Resistors") (part "Res 5K6 0603"))
    )
    (comp (ref "R32")
      (value "8K2")
      (footprint "0603")
      (description "Lead Free Thick Film Chip Resistor 0603 ±1%")
      (fields
        (field (name "LCSC PART NUMBER") "C25981")
        (field (name "TOLERANCE") "±1%")
        (field (name "POWER") "0.1W")
        (field (name "PACKAGE") "0603")
        (field (name "POPULATE") "CRITICAL")
        (field (name "Comment") "0603WAF8201T5E")
      )
      (libsource (lib "Uniroyal Resistors") (part "Res 8K2 0603"))
    )
    (comp (ref "R33")
      (value "120R")
      (footprint "0603")
      (description "Lead Free Thick Film Chip Resistor 0603 ±1%")
      (fields
        (field (name "LCSC PART NUMBER") "C22787")
        (field (name "TOLERANCE") "±1%")
        (field (name "POWER") "0.1W")
        (field (name "PACKAGE") "0603")
        (field (name "POPULATE") "CRITICAL")
        (field (name "Comment") "0603WAF1200T5E")
      )
      (libsource (lib "Uniroyal Resistors") (part "Res 120R 0603"))
    )
    (comp (ref "S1")
      (value "SK12D07L4B")
      (footprint "SK12D07L4B")
      (description "Switch Toggle Slider THT Right Angle 0A3 50V")
      (fields
        (field (name "VOLTAGE") "50V")
        (field (name "CURRENT") "0A3")
        (field (name "PLACEMENT") "CRITICAL")
        (field (name "LCSC PART NUMBER") "C480340")
      )
      (libsource (lib "Slide Switches") (part "SW Toggle Slide Right Angle 0A3 50V"))
    )
    (comp (ref "TP1")
      (value "Test Point")
      (footprint "Test Point 0.6")
      (description "Test Point. Multiple pad options.")
      (libsource (lib "Test Points") (part "Test Point"))
    )
    (comp (ref "TP2")
      (value "Test Point")
      (footprint "Test Point 0.6")
      (description "Test Point. Multiple pad options.")
      (libsource (lib "Test Points") (part "Test Point"))
    )
    (comp (ref "TP3")
      (value "Test Point")
      (footprint "Test Point 0.6")
      (description "Test Point. Multiple pad options.")
      (libsource (lib "Test Points") (part "Test Point"))
    )
    (comp (ref "TP4")
      (value "Test Point")
      (footprint "Test Point 0.6")
      (description "Test Point. Multiple pad options.")
      (libsource (lib "Test Points") (part "Test Point"))
    )
    (comp (ref "TP5")
      (value "Test Point")
      (footprint "Test Point 0.6")
      (description "Test Point. Multiple pad options.")
      (libsource (lib "Test Points") (part "Test Point"))
    )
    (comp (ref "TP6")
      (value "Test Point")
      (footprint "Test Point 0.6")
      (description "Test Point. Multiple pad options.")
      (libsource (lib "Test Points") (part "Test Point"))
    )
    (comp (ref "TP7")
      (value "Test Point")
      (footprint "Test Point 0.6")
      (description "Test Point. Multiple pad options.")
      (libsource (lib "Test Points") (part "Test Point"))
    )
    (comp (ref "TP8")
      (value "Test Point")
      (footprint "Test Point 0.6")
      (description "Test Point. Multiple pad options.")
      (libsource (lib "Test Points") (part "Test Point"))
    )
    (comp (ref "TP9")
      (value "Test Point")
      (footprint "Test Point 0.6")
      (description "Test Point. Multiple pad options.")
      (libsource (lib "Test Points") (part "Test Point"))
    )
    (comp (ref "TP10")
      (value "Test Point")
      (footprint "Test Point 0.6")
      (description "Test Point. Multiple pad options.")
      (libsource (lib "Test Points") (part "Test Point"))
    )
    (comp (ref "TP11")
      (value "Test Point")
      (footprint "Test Point 0.6")
      (description "Test Point. Multiple pad options.")
      (libsource (lib "Test Points") (part "Test Point"))
    )
    (comp (ref "U1")
      (value "LM317LBDR2G")
      (footprint "SOIC-8 NB")
      (description "100mA, 1V2 - 37V Adjustable Output, Positive Voltage Regulator")
      (fields
        (field (name "MANUFACTURER") "ON Semiconductor")
        (field (name "LCSC PART NUMBER") "C274645")
        (field (name "PLACEMENT") "CRITICAL")
      )
      (libsource (lib "Linear Regulators") (part "LM317LBDR2G"))
    )
    (comp (ref "U2")
      (value "MC34063ADR2G")
      (footprint "SOIC-8 NB")
      (description "1A5 Step-Up, Step-Down, Inverting Switching Reulator")
      (fields
        (field (name "MANUFACTURER") "ON Semi")
        (field (name "LCSC PART NUMBER") "C32078")
        (field (name "PLACEMENT") "CRITICAL")
      )
      (libsource (lib "Switching Regulators") (part "MC34063ADR2G"))
    )
    (comp (ref "U3")
      (value "LM337LMX")
      (footprint "SOIC-8 D (R-PDSO-G8)")
      (description "100mA, -1V2 to -37V Adjustable Negative Voltage Regulator")
      (fields
        (field (name "MANUFACTURER") "Texas Instruments")
        (field (name "LCSC PART NUMBER") "C7947")
        (field (name "PLACEMENT") "CRITICAL")
      )
      (libsource (lib "Linear Regulators") (part "LM337LMX"))
    )
    (comp (ref "U4")
      (value "MC34063ADR2G")
      (footprint "SOIC-8 NB")
      (description "1A5 Step-Up, Step-Down, Inverting Switching Reulator")
      (fields
        (field (name "MANUFACTURER") "ON Semi")
        (field (name "LCSC PART NUMBER") "C32078")
        (field (name "PLACEMENT") "CRITICAL")
      )
      (libsource (lib "Switching Regulators") (part "MC34063ADR2G"))
    )
    (comp (ref "XW1")
      (value "Short 2 Nets")
      (footprint "Short 0.5mm 2 Net")
      (description "Net Tie 2 Nets")
      (libsource (lib "Passives") (part "Short 2 Nets"))
    )
    (comp (ref "XW2")
      (value "Short 2 Nets")
      (footprint "Short 0.5mm 2 Net")
      (description "Net Tie 2 Nets")
      (libsource (lib "Passives") (part "Short 2 Nets"))
    )
    (comp (ref "XW3")
      (value "Short 2 Nets")
      (footprint "Short 0.5mm 2 Net")
      (description "Net Tie 2 Nets")
      (libsource (lib "Passives") (part "Short 2 Nets"))
    )
    (comp (ref "XW4")
      (value "Short 2 Nets")
      (footprint "Short 0.5mm 2 Net")
      (description "Net Tie 2 Nets")
      (libsource (lib "Passives") (part "Short 2 Nets"))
    )
  )
  (nets
    (net (code "1") (name "/5V_LED_A") (class "Default")
      (node (ref "D1") (pin "A") (pinfunction "A_A") (pintype "passive"))
      (node (ref "R1") (pin "2") (pinfunction "2_2") (pintype "passive"))
    )
    (net (code "2") (name "/BOOST_VF_FB") (class "Default")
      (node (ref "Q3") (pin "3") (pinfunction "D_3") (pintype "passive"))
      (node (ref "R17") (pin "2") (pinfunction "2_2") (pintype "passive"))
    )
    (net (code "3") (name "/INV_VF_FB") (class "Default")
      (node (ref "Q8") (pin "3") (pinfunction "D_3") (pintype "passive"))
      (node (ref "R31") (pin "1") (pinfunction "1_1") (pintype "passive"))
    )
    (net (code "4") (name "/LM317_NC_1") (class "Default")
      (node (ref "U1") (pin "5") (pinfunction "NC_5") (pintype "passive+no_connect"))
    )
    (net (code "5") (name "/LM317_NC_2") (class "Default")
      (node (ref "U1") (pin "8") (pinfunction "NC_8") (pintype "passive+no_connect"))
    )
    (net (code "6") (name "/LM337_NC_1") (class "Default")
      (node (ref "U3") (pin "5") (pinfunction "NC_5") (pintype "passive+no_connect"))
    )
    (net (code "7") (name "/LM337_NC_2") (class "Default")
      (node (ref "U3") (pin "8") (pinfunction "NC_8") (pintype "passive+no_connect"))
    )
    (net (code "8") (name "/N1V25_NREG_ADJ") (class "Default")
      (node (ref "C19") (pin "1") (pinfunction "1_1") (pintype "passive"))
      (node (ref "R18") (pin "2") (pinfunction "2_2") (pintype "passive"))
      (node (ref "R19") (pin "1") (pinfunction "1_1") (pintype "passive"))
      (node (ref "R23") (pin "1") (pinfunction "1_1") (pintype "passive"))
      (node (ref "R24") (pin "1") (pinfunction "1_1") (pintype "passive"))
      (node (ref "U3") (pin "4") (pinfunction "ADJ_4") (pintype "input"))
    )
    (net (code "9") (name "/N1V25_S0_INV_FB") (class "Default")
      (node (ref "R28") (pin "1") (pinfunction "1_1") (pintype "passive"))
      (node (ref "R29") (pin "1") (pinfunction "1_1") (pintype "passive"))
      (node (ref "R31") (pin "2") (pinfunction "2_2") (pintype "passive"))
      (node (ref "U4") (pin "5") (pinfunction "COMP_5") (pintype "input"))
    )
    (net (code "10") (name "/P1V25_PREG_ADJ") (class "Default")
      (node (ref "C7") (pin "1") (pinfunction "1_1") (pintype "passive"))
      (node (ref "R11") (pin "1") (pinfunction "1_1") (pintype "passive"))
      (node (ref "R3") (pin "2") (pinfunction "2_2") (pintype "passive"))
      (node (ref "R5") (pin "1") (pinfunction "1_1") (pintype "passive"))
      (node (ref "R8") (pin "3") (pinfunction "3_3") (pintype "passive"))
      (node (ref "U1") (pin "4") (pinfunction "ADJ_4") (pintype "input"))
    )
    (net (code "11") (name "/P1V25_S0_BOOST_FB") (class "Default")
      (node (ref "R13") (pin "1") (pinfunction "1_1") (pintype "passive"))
      (node (ref "R15") (pin "1") (pinfunction "1_1") (pintype "passive"))
      (node (ref "R17") (pin "1") (pinfunction "1_1") (pintype "passive"))
      (node (ref "U2") (pin "5") (pinfunction "COMP_5") (pintype "input"))
    )
    (net (code "12") (name "/P5V0_S0H_BOOST") (class "Default")
      (node (ref "D2") (pin "2") (pinfunction "A_2") (pintype "passive"))
      (node (ref "L1") (pin "1") (pinfunction "1_1") (pintype "passive"))
      (node (ref "R4") (pin "1") (pinfunction "1_1") (pintype "passive"))
      (node (ref "R7") (pin "1") (pinfunction "1_1") (pintype "passive"))
      (node (ref "XW1") (pin "2") (pinfunction "2_2") (pintype "passive"))
    )
    (net (code "13") (name "/P5V0_S0_BOOSTVCC_N") (class "Default")
      (node (ref "U2") (pin "7") (pinfunction "SENCE_7") (pintype "input"))
      (node (ref "XW1") (pin "1") (pinfunction "1_1") (pintype "passive"))
    )
    (net (code "14") (name "/P5V0_S0_BOOSTVCC_P") (class "Default")
      (node (ref "C8") (pin "1") (pinfunction "1_1") (pintype "passive"))
      (node (ref "U2") (pin "6") (pinfunction "VCC_6") (pintype "tri_state"))
      (node (ref "XW2") (pin "1") (pinfunction "1_1") (pintype "passive"))
    )
    (net (code "15") (name "/P5V0_S0_INVVCC_N") (class "Default")
      (node (ref "U4") (pin "7") (pinfunction "SENCE_7") (pintype "input"))
      (node (ref "XW3") (pin "1") (pinfunction "1_1") (pintype "passive"))
    )
    (net (code "16") (name "/P5V0_S0_INVVCC_P") (class "Default")
      (node (ref "C17") (pin "1") (pinfunction "1_1") (pintype "passive"))
      (node (ref "U4") (pin "6") (pinfunction "VCC_6") (pintype "tri_state"))
      (node (ref "XW4") (pin "1") (pinfunction "1_1") (pintype "passive"))
    )
    (net (code "17") (name "/PBOOST_S0H_SW") (class "Default")
      (node (ref "D3") (pin "2") (pinfunction "A_2") (pintype "passive"))
      (node (ref "L1") (pin "2") (pinfunction "2_2") (pintype "passive"))
      (node (ref "TP3") (pin "1") (pinfunction "1_1") (pintype "passive"))
      (node (ref "U2") (pin "1") (pinfunction "SWC_1") (pintype "open_collector"))
    )
    (net (code "18") (name "/PDRIVE_S0_BOOST") (class "Default")
      (node (ref "R4") (pin "2") (pinfunction "2_2") (pintype "passive"))
      (node (ref "U2") (pin "8") (pinfunction "DRIVE_8") (pintype "open_collector"))
    )
    (net (code "19") (name "/PINV_S0H_SW") (class "Default")
      (node (ref "D5") (pin "1") (pinfunction "K_1") (pintype "passive"))
      (node (ref "L2") (pin "2") (pinfunction "2_2") (pintype "passive"))
      (node (ref "TP9") (pin "1") (pinfunction "1_1") (pintype "passive"))
      (node (ref "U4") (pin "2") (pinfunction "SWE_2") (pintype "passive"))
    )
    (net (code "20") (name "/PP5V0_G3H_FUSE") (class "Default")
      (node (ref "F1") (pin "2") (pinfunction "2_2") (pintype "passive"))
      (node (ref "Q1") (pin "2") (pinfunction "S_2") (pintype "passive"))
      (node (ref "S1") (pin "3") (pinfunction "3_3") (pintype "passive"))
      (node (ref "TP2") (pin "1") (pinfunction "1_1") (pintype "passive"))
    )
    (net (code "21") (name "/PP5V0_G3H_USB") (class "Default")
      (node (ref "C1") (pin "1") (pinfunction "1_1") (pintype "passive"))
      (node (ref "F1") (pin "1") (pinfunction "1_1") (pintype "passive"))
      (node (ref "P1") (pin "1") (pinfunction "VCC_1") (pintype "power_in"))
      (node (ref "TP1") (pin "1") (pinfunction "1_1") (pintype "passive"))
    )
    (net (code "22") (name "/PP5V0_S0H_INV") (class "Default")
      (node (ref "R20") (pin "1") (pinfunction "1_1") (pintype "passive"))
      (node (ref "U4") (pin "1") (pinfunction "SWC_1") (pintype "open_collector"))
      (node (ref "U4") (pin "8") (pinfunction "DRIVE_8") (pintype "open_collector"))
      (node (ref "XW3") (pin "2") (pinfunction "2_2") (pintype "passive"))
    )
    (net (code "23") (name "/SW_G") (class "Default")
      (node (ref "Q1") (pin "1") (pinfunction "G_1") (pintype "passive"))
      (node (ref "R2") (pin "2") (pinfunction "2_2") (pintype "passive"))
    )
    (net (code "24") (name "/SW_T") (class "Default")
      (node (ref "R2") (pin "1") (pinfunction "1_1") (pintype "passive"))
      (node (ref "S1") (pin "2") (pinfunction "2_2") (pintype "passive"))
    )
    (net (code "25") (name "/USB_DN") (class "Default")
      (node (ref "P1") (pin "2") (pinfunction "D-_2") (pintype "bidirectional"))
    )
    (net (code "26") (name "/USB_DP") (class "Default")
      (node (ref "P1") (pin "3") (pinfunction "D+_3") (pintype "bidirectional"))
    )
    (net (code "27") (name "/USB_ID") (class "Default")
      (node (ref "P1") (pin "4") (pinfunction "ID_4") (pintype "passive+no_connect"))
    )
    (net (code "28") (name "GND") (class "Default")
      (node (ref "C1") (pin "2") (pinfunction "2_2") (pintype "passive"))
      (node (ref "C11") (pin "2") (pinfunction "2_2") (pintype "passive"))
      (node (ref "C12") (pin "2") (pinfunction "2_2") (pintype "passive"))
      (node (ref "C13") (pin "2") (pinfunction "2_2") (pintype "passive"))
      (node (ref "C14") (pin "2") (pinfunction "2_2") (pintype "passive"))
      (node (ref "C15") (pin "2") (pinfunction "2_2") (pintype "passive"))
      (node (ref "C16") (pin "2") (pinfunction "2_2") (pintype "passive"))
      (node (ref "C17") (pin "2") (pinfunction "2_2") (pintype "passive"))
      (node (ref "C19") (pin "2") (pinfunction "2_2") (pintype "passive"))
      (node (ref "C2") (pin "2") (pinfunction "2_2") (pintype "passive"))
      (node (ref "C22") (pin "1") (pinfunction "1_1") (pintype "passive"))
      (node (ref "C23") (pin "1") (pinfunction "1_1") (pintype "passive"))
      (node (ref "C24") (pin "1") (pinfunction "1_1") (pintype "passive"))
      (node (ref "C25") (pin "1") (pinfunction "1_1") (pintype "passive"))
      (node (ref "C3") (pin "2") (pinfunction "2_2") (pintype "passive"))
      (node (ref "C4") (pin "2") (pinfunction "2_2") (pintype "passive"))
      (node (ref "C5") (pin "2") (pinfunction "2_2") (pintype "passive"))
      (node (ref "C7") (pin "2") (pinfunction "2_2") (pintype "passive"))
      (node (ref "C8") (pin "2") (pinfunction "2_2") (pintype "passive"))
      (node (ref "C9") (pin "2") (pinfunction "2_2") (pintype "passive"))
      (node (ref "D1") (pin "K") (pinfunction "K_K") (pintype "passive"))
      (node (ref "D6") (pin "K") (pinfunction "K_K") (pintype "passive"))
      (node (ref "L2") (pin "1") (pinfunction "1_1") (pintype "passive"))
      (node (ref "P1") (pin "5") (pinfunction "GND_5") (pintype "power_in"))
      (node (ref "P1") (pin "6") (pinfunction "SHIELD_6") (pintype "passive"))
      (node (ref "P2") (pin "2") (pinfunction "2_2") (pintype "passive"))
      (node (ref "P2") (pin "4") (pinfunction "4_4") (pintype "passive"))
      (node (ref "P3") (pin "10") (pinfunction "10_10") (pintype "passive"))
      (node (ref "P3") (pin "2") (pinfunction "2_2") (pintype "passive"))
      (node (ref "P3") (pin "4") (pinfunction "4_4") (pintype "passive"))
      (node (ref "P3") (pin "6") (pinfunction "6_6") (pintype "passive"))
      (node (ref "P3") (pin "8") (pinfunction "8_8") (pintype "passive"))
      (node (ref "P4") (pin "10") (pinfunction "10_10") (pintype "passive"))
      (node (ref "P4") (pin "2") (pinfunction "2_2") (pintype "passive"))
      (node (ref "P4") (pin "4") (pinfunction "4_4") (pintype "passive"))
      (node (ref "P4") (pin "6") (pinfunction "6_6") (pintype "passive"))
      (node (ref "P4") (pin "8") (pinfunction "8_8") (pintype "passive"))
      (node (ref "P5") (pin "3") (pinfunction "3_3") (pintype "passive"))
      (node (ref "P5") (pin "4") (pinfunction "4_4") (pintype "passive"))
      (node (ref "P6") (pin "1") (pinfunction "1_1") (pintype "passive"))
      (node (ref "P6") (pin "2") (pinfunction "2_2") (pintype "passive"))
      (node (ref "Q4") (pin "2") (pinfunction "S_2") (pintype "passive"))
      (node (ref "R11") (pin "2") (pinfunction "2_2") (pintype "passive"))
      (node (ref "R14") (pin "1") (pinfunction "1_1") (pintype "passive"))
      (node (ref "R15") (pin "2") (pinfunction "2_2") (pintype "passive"))
      (node (ref "R23") (pin "2") (pinfunction "2_2") (pintype "passive"))
      (node (ref "R23") (pin "3") (pinfunction "3_3") (pintype "passive"))
      (node (ref "R23") (pin "4") (pinfunction "MH_4") (pintype "passive"))
      (node (ref "R23") (pin "5") (pinfunction "MH_5") (pintype "passive"))
      (node (ref "R24") (pin "2") (pinfunction "2_2") (pintype "passive"))
      (node (ref "R29") (pin "2") (pinfunction "2_2") (pintype "passive"))
      (node (ref "R33") (pin "1") (pinfunction "1_1") (pintype "passive"))
      (node (ref "R8") (pin "1") (pinfunction "1_1") (pintype "passive"))
      (node (ref "R8") (pin "2") (pinfunction "2_2") (pintype "passive"))
      (node (ref "R8") (pin "4") (pinfunction "MH_4") (pintype "passive"))
      (node (ref "R8") (pin "5") (pinfunction "MH_5") (pintype "passive"))
      (node (ref "S1") (pin "EH") (pinfunction "MH_EH") (pintype "passive"))
      (node (ref "TP11") (pin "1") (pinfunction "1_1") (pintype "passive"))
      (node (ref "U2") (pin "2") (pinfunction "SWE_2") (pintype "passive"))
      (node (ref "U2") (pin "4") (pinfunction "GND_4") (pintype "power_in"))
    )
    (net (code "29") (name "Net-(D4-PadA)") (class "Default")
      (node (ref "D4") (pin "A") (pinfunction "A_A") (pintype "passive"))
      (node (ref "R6") (pin "1") (pinfunction "1_1") (pintype "passive"))
    )
    (net (code "30") (name "Net-(D6-PadA)") (class "Default")
      (node (ref "D6") (pin "A") (pinfunction "A_A") (pintype "passive"))
      (node (ref "R27") (pin "2") (pinfunction "2_2") (pintype "passive"))
    )
    (net (code "31") (name "Net-(Q2-D)") (class "Default")
      (node (ref "Q2") (pin "3") (pinfunction "D_3") (pintype "passive"))
      (node (ref "Q4") (pin "1") (pinfunction "G_1") (pintype "passive"))
      (node (ref "R14") (pin "2") (pinfunction "2_2") (pintype "passive"))
    )
    (net (code "32") (name "Net-(Q2-G)") (class "Default")
      (node (ref "Q2") (pin "1") (pinfunction "G_1") (pintype "passive"))
      (node (ref "R5") (pin "2") (pinfunction "2_2") (pintype "passive"))
    )
    (net (code "33") (name "Net-(Q3-G)") (class "Default")
      (node (ref "Q3") (pin "1") (pinfunction "G_1") (pintype "passive"))
      (node (ref "R12") (pin "2") (pinfunction "2_2") (pintype "passive"))
    )
    (net (code "34") (name "Net-(Q4-D)") (class "Default")
      (node (ref "D4") (pin "K") (pinfunction "K_K") (pintype "passive"))
      (node (ref "Q4") (pin "3") (pinfunction "D_3") (pintype "passive"))
    )
    (net (code "35") (name "Net-(Q5-B)") (class "Default")
      (node (ref "C10") (pin "1") (pinfunction "1_1") (pintype "passive"))
      (node (ref "Q5") (pin "1") (pinfunction "B_1") (pintype "passive"))
      (node (ref "R16") (pin "1") (pinfunction "1_1") (pintype "passive"))
      (node (ref "R9") (pin "2") (pinfunction "2_2") (pintype "passive"))
    )
    (net (code "36") (name "Net-(Q5-C)") (class "Default")
      (node (ref "C10") (pin "2") (pinfunction "2_2") (pintype "passive"))
      (node (ref "C6") (pin "2") (pinfunction "2_2") (pintype "passive"))
      (node (ref "Q5") (pin "3") (pinfunction "C_3") (pintype "passive"))
      (node (ref "R10") (pin "2") (pinfunction "2_2") (pintype "passive"))
      (node (ref "R12") (pin "1") (pinfunction "1_1") (pintype "passive"))
    )
    (net (code "37") (name "Net-(Q6-D)") (class "Default")
      (node (ref "Q6") (pin "3") (pinfunction "D_3") (pintype "passive"))
      (node (ref "R21") (pin "1") (pinfunction "1_1") (pintype "passive"))
    )
    (net (code "38") (name "Net-(Q6-G)") (class "Default")
      (node (ref "Q6") (pin "1") (pinfunction "G_1") (pintype "passive"))
      (node (ref "R19") (pin "2") (pinfunction "2_2") (pintype "passive"))
    )
    (net (code "39") (name "Net-(Q7-D)") (class "Default")
      (node (ref "Q7") (pin "3") (pinfunction "D_3") (pintype "passive"))
      (node (ref "R27") (pin "1") (pinfunction "1_1") (pintype "passive"))
    )
    (net (code "40") (name "Net-(Q7-G)") (class "Default")
      (node (ref "Q7") (pin "1") (pinfunction "G_1") (pintype "passive"))
      (node (ref "R21") (pin "2") (pinfunction "2_2") (pintype "passive"))
      (node (ref "R22") (pin "1") (pinfunction "1_1") (pintype "passive"))
    )
    (net (code "41") (name "Net-(Q8-G)") (class "Default")
      (node (ref "Q8") (pin "1") (pinfunction "G_1") (pintype "passive"))
      (node (ref "R30") (pin "2") (pinfunction "2_2") (pintype "passive"))
    )
    (net (code "42") (name "Net-(Q9-B)") (class "Default")
      (node (ref "C21") (pin "1") (pinfunction "1_1") (pintype "passive"))
      (node (ref "Q9") (pin "1") (pinfunction "B_1") (pintype "passive"))
      (node (ref "R25") (pin "2") (pinfunction "2_2") (pintype "passive"))
      (node (ref "R32") (pin "1") (pinfunction "1_1") (pintype "passive"))
    )
    (net (code "43") (name "Net-(Q9-C)") (class "Default")
      (node (ref "C20") (pin "2") (pinfunction "2_2") (pintype "passive"))
      (node (ref "C21") (pin "2") (pinfunction "2_2") (pintype "passive"))
      (node (ref "Q9") (pin "3") (pinfunction "C_3") (pintype "passive"))
      (node (ref "R26") (pin "2") (pinfunction "2_2") (pintype "passive"))
      (node (ref "R30") (pin "1") (pinfunction "1_1") (pintype "passive"))
    )
    (net (code "44") (name "Net-(R33-Pad2)") (class "Default")
      (node (ref "R33") (pin "2") (pinfunction "2_2") (pintype "passive"))
      (node (ref "S1") (pin "1") (pinfunction "1_1") (pintype "passive"))
    )
    (net (code "45") (name "Net-(U2-TIMC)") (class "Default")
      (node (ref "C9") (pin "1") (pinfunction "1_1") (pintype "passive"))
      (node (ref "TP6") (pin "1") (pinfunction "1_1") (pintype "passive"))
      (node (ref "U2") (pin "3") (pinfunction "TIMC_3") (pintype "passive"))
    )
    (net (code "46") (name "Net-(U4-TIMC)") (class "Default")
      (node (ref "C18") (pin "1") (pinfunction "1_1") (pintype "passive"))
      (node (ref "TP10") (pin "1") (pinfunction "1_1") (pintype "passive"))
      (node (ref "U4") (pin "3") (pinfunction "TIMC_3") (pintype "passive"))
    )
    (net (code "47") (name "PN_VREG_S0H") (class "Default")
      (node (ref "C15") (pin "1") (pinfunction "1_1") (pintype "passive"))
      (node (ref "P2") (pin "5") (pinfunction "5_5") (pintype "passive"))
      (node (ref "P4") (pin "1") (pinfunction "1_1") (pintype "passive"))
      (node (ref "P4") (pin "3") (pinfunction "3_3") (pintype "passive"))
      (node (ref "P4") (pin "5") (pinfunction "5_5") (pintype "passive"))
      (node (ref "P4") (pin "7") (pinfunction "7_7") (pintype "passive"))
      (node (ref "P4") (pin "9") (pinfunction "9_9") (pintype "passive"))
      (node (ref "P6") (pin "3") (pinfunction "3_3") (pintype "passive"))
      (node (ref "P6") (pin "4") (pinfunction "4_4") (pintype "passive"))
      (node (ref "Q6") (pin "2") (pinfunction "S_2") (pintype "passive"))
      (node (ref "R18") (pin "1") (pinfunction "1_1") (pintype "passive"))
      (node (ref "R25") (pin "1") (pinfunction "1_1") (pintype "passive"))
      (node (ref "TP8") (pin "1") (pinfunction "1_1") (pintype "passive"))
      (node (ref "U3") (pin "1") (pinfunction "VOUT_1") (pintype "power_in"))
    )
    (net (code "48") (name "PN_VTRACK_S0H") (class "Default")
      (node (ref "C16") (pin "1") (pinfunction "1_1") (pintype "passive"))
      (node (ref "C18") (pin "2") (pinfunction "2_2") (pintype "passive"))
      (node (ref "C20") (pin "1") (pinfunction "1_1") (pintype "passive"))
      (node (ref "C22") (pin "2") (pinfunction "2_2") (pintype "passive"))
      (node (ref "C23") (pin "2") (pinfunction "2_2") (pintype "passive"))
      (node (ref "C24") (pin "2") (pinfunction "2_2") (pintype "passive"))
      (node (ref "C25") (pin "2") (pinfunction "2_2") (pintype "passive"))
      (node (ref "D5") (pin "2") (pinfunction "A_2") (pintype "passive"))
      (node (ref "Q8") (pin "2") (pinfunction "S_2") (pintype "passive"))
      (node (ref "Q9") (pin "2") (pinfunction "E_2") (pintype "passive"))
      (node (ref "R26") (pin "1") (pinfunction "1_1") (pintype "passive"))
      (node (ref "R28") (pin "2") (pinfunction "2_2") (pintype "passive"))
      (node (ref "R32") (pin "2") (pinfunction "2_2") (pintype "passive"))
      (node (ref "TP7") (pin "1") (pinfunction "1_1") (pintype "passive"))
      (node (ref "U3") (pin "2") (pinfunction "VIN_2") (pintype "power_in"))
      (node (ref "U3") (pin "3") (pinfunction "VIN_3") (pintype "power_in"))
      (node (ref "U3") (pin "6") (pinfunction "VIN_6") (pintype "power_in"))
      (node (ref "U3") (pin "7") (pinfunction "VIN_7") (pintype "power_in"))
      (node (ref "U4") (pin "4") (pinfunction "GND_4") (pintype "power_in"))
    )
    (net (code "49") (name "PP5V0_S0") (class "Default")
      (node (ref "R7") (pin "2") (pinfunction "2_2") (pintype "passive"))
      (node (ref "XW2") (pin "2") (pinfunction "2_2") (pintype "passive"))
    )
    (net (code "50") (name "PP5V0_S0H") (class "Default")
      (node (ref "C2") (pin "1") (pinfunction "1_1") (pintype "passive"))
      (node (ref "C3") (pin "1") (pinfunction "1_1") (pintype "passive"))
      (node (ref "P2") (pin "3") (pinfunction "3_3") (pintype "passive"))
      (node (ref "Q1") (pin "3") (pinfunction "D_3") (pintype "passive"))
      (node (ref "Q7") (pin "2") (pinfunction "S_2") (pintype "passive"))
      (node (ref "R1") (pin "1") (pinfunction "1_1") (pintype "passive"))
      (node (ref "R20") (pin "2") (pinfunction "2_2") (pintype "passive"))
      (node (ref "R22") (pin "2") (pinfunction "2_2") (pintype "passive"))
      (node (ref "R6") (pin "2") (pinfunction "2_2") (pintype "passive"))
      (node (ref "XW4") (pin "2") (pinfunction "2_2") (pintype "passive"))
    )
    (net (code "51") (name "PPVTRACK_S0H") (class "Default")
      (node (ref "C11") (pin "1") (pinfunction "1_1") (pintype "passive"))
      (node (ref "C12") (pin "1") (pinfunction "1_1") (pintype "passive"))
      (node (ref "C13") (pin "1") (pinfunction "1_1") (pintype "passive"))
      (node (ref "C14") (pin "1") (pinfunction "1_1") (pintype "passive"))
      (node (ref "C4") (pin "1") (pinfunction "1_1") (pintype "passive"))
      (node (ref "C6") (pin "1") (pinfunction "1_1") (pintype "passive"))
      (node (ref "D2") (pin "1") (pinfunction "K_1") (pintype "passive"))
      (node (ref "D3") (pin "1") (pinfunction "K_1") (pintype "passive"))
      (node (ref "Q3") (pin "2") (pinfunction "S_2") (pintype "passive"))
      (node (ref "R10") (pin "1") (pinfunction "1_1") (pintype "passive"))
      (node (ref "R13") (pin "2") (pinfunction "2_2") (pintype "passive"))
      (node (ref "R9") (pin "1") (pinfunction "1_1") (pintype "passive"))
      (node (ref "TP4") (pin "1") (pinfunction "1_1") (pintype "passive"))
      (node (ref "U1") (pin "1") (pinfunction "VIN_1") (pintype "power_in"))
    )
    (net (code "52") (name "PP_VREG_S0H") (class "Default")
      (node (ref "C5") (pin "1") (pinfunction "1_1") (pintype "passive"))
      (node (ref "P2") (pin "1") (pinfunction "1_1") (pintype "passive"))
      (node (ref "P3") (pin "1") (pinfunction "1_1") (pintype "passive"))
      (node (ref "P3") (pin "3") (pinfunction "3_3") (pintype "passive"))
      (node (ref "P3") (pin "5") (pinfunction "5_5") (pintype "passive"))
      (node (ref "P3") (pin "7") (pinfunction "7_7") (pintype "passive"))
      (node (ref "P3") (pin "9") (pinfunction "9_9") (pintype "passive"))
      (node (ref "P5") (pin "1") (pinfunction "1_1") (pintype "passive"))
      (node (ref "P5") (pin "2") (pinfunction "2_2") (pintype "passive"))
      (node (ref "Q2") (pin "2") (pinfunction "S_2") (pintype "passive"))
      (node (ref "Q5") (pin "2") (pinfunction "E_2") (pintype "passive"))
      (node (ref "R16") (pin "2") (pinfunction "2_2") (pintype "passive"))
      (node (ref "R3") (pin "1") (pinfunction "1_1") (pintype "passive"))
      (node (ref "TP5") (pin "1") (pinfunction "1_1") (pintype "passive"))
      (node (ref "U1") (pin "2") (pinfunction "VOUT_2") (pintype "power_in"))
      (node (ref "U1") (pin "3") (pinfunction "VOUT_3") (pintype "power_in"))
      (node (ref "U1") (pin "6") (pinfunction "VOUT_6") (pintype "power_in"))
      (node (ref "U1") (pin "7") (pinfunction "VOUT_7") (pintype "power_in"))
    )
  )
)
